# LCD_ControlRev2.net
KiCad netlist of a schematic drawn in EAGLE
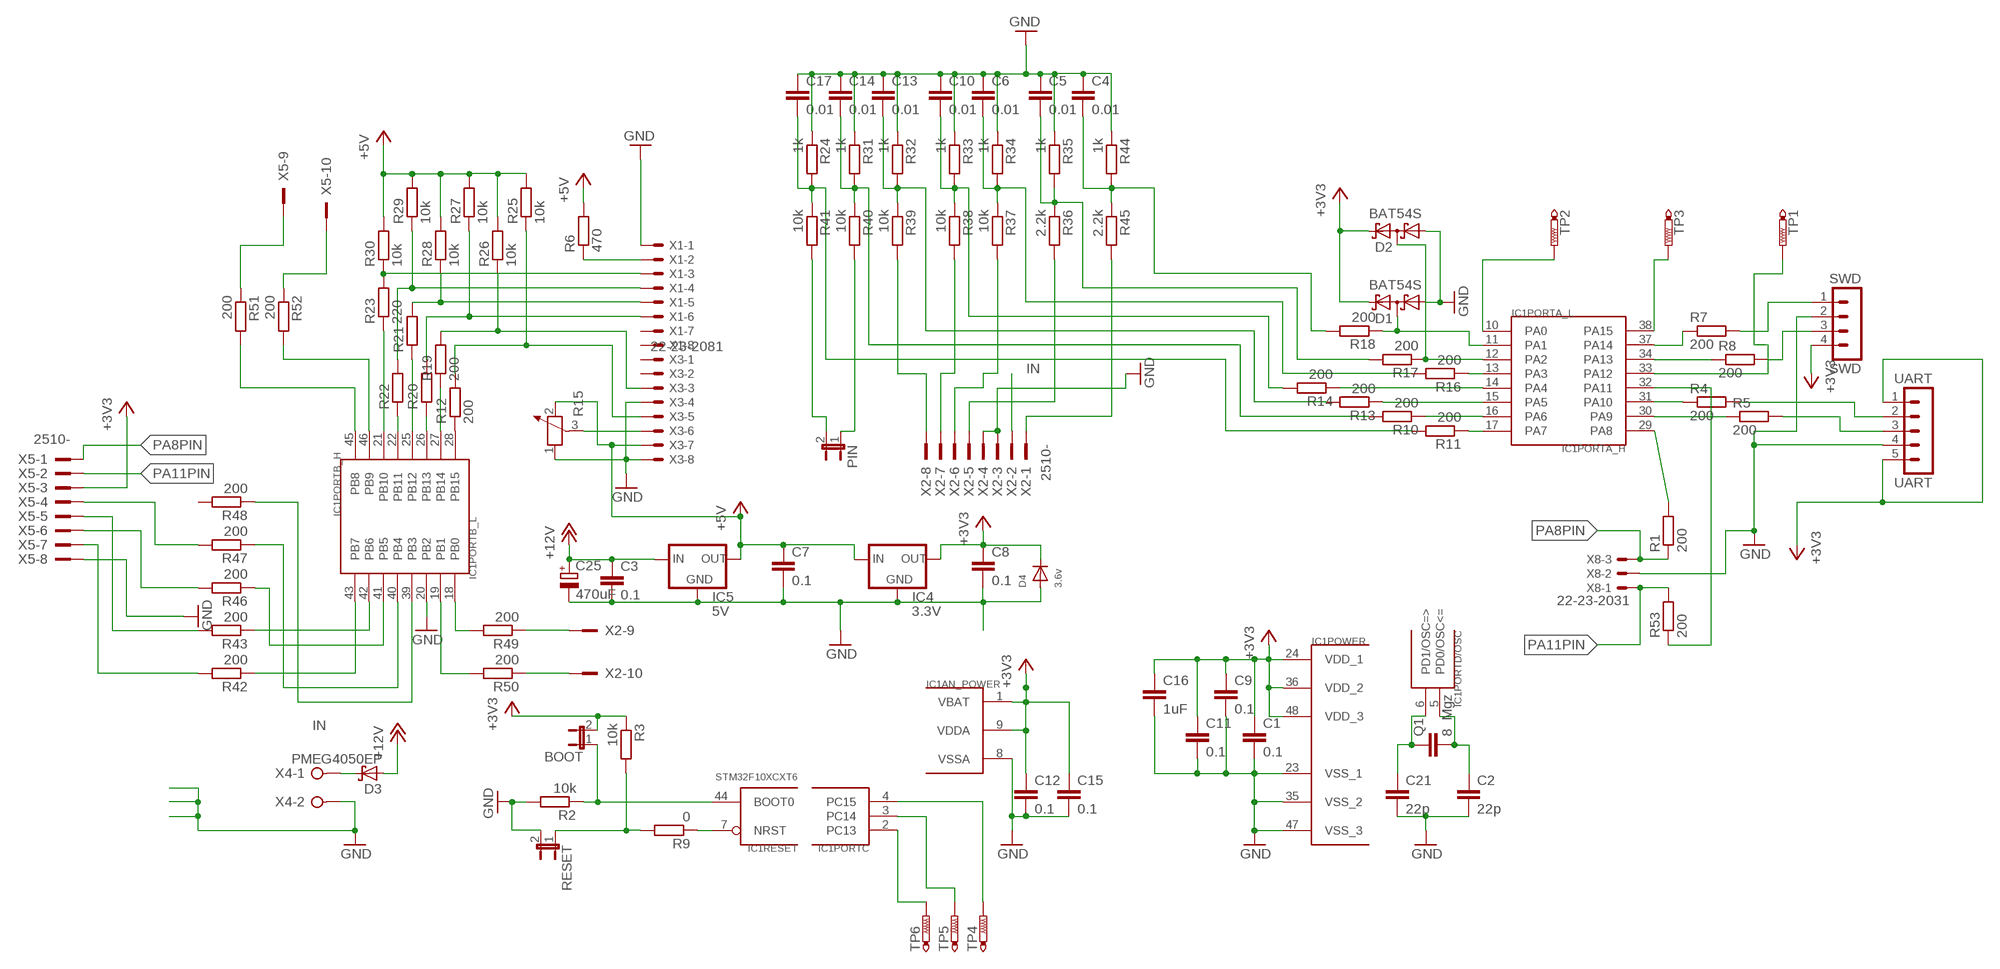
[diagram p0: schematic, sheet 1]

(export (version "E")
  (design (tool "Eeschema 10.0.6"))
  (components
    (comp (ref "BOOT")
      (value "JP1E")
      (footprint "eagle-import:JP1")
      (libsource (lib "eagle-import") (part "JP1E"))
    )
    (comp (ref "C1")
      (value "0.1")
      (footprint "eagle-import:C0402")
      (libsource (lib "eagle-import") (part "C-EUC0402"))
    )
    (comp (ref "C2")
      (value "22p")
      (footprint "eagle-import:C0603")
      (libsource (lib "eagle-import") (part "C-EUC0603"))
    )
    (comp (ref "C3")
      (value "0.1")
      (footprint "eagle-import:C1206")
      (libsource (lib "eagle-import") (part "C-EUC1206"))
    )
    (comp (ref "C4")
      (value "0.01")
      (footprint "eagle-import:C0603")
      (libsource (lib "eagle-import") (part "rcl_334_C-EUC0603"))
    )
    (comp (ref "C5")
      (value "0.01")
      (footprint "eagle-import:C0603")
      (libsource (lib "eagle-import") (part "rcl_334_C-EUC0603"))
    )
    (comp (ref "C6")
      (value "0.01")
      (footprint "eagle-import:C0603")
      (libsource (lib "eagle-import") (part "rcl_334_C-EUC0603"))
    )
    (comp (ref "C7")
      (value "0.1")
      (footprint "eagle-import:C1206")
      (libsource (lib "eagle-import") (part "C-EUC1206"))
    )
    (comp (ref "C8")
      (value "0.1")
      (footprint "eagle-import:C1206")
      (libsource (lib "eagle-import") (part "C-EUC1206"))
    )
    (comp (ref "C9")
      (value "0.1")
      (footprint "eagle-import:C0402")
      (libsource (lib "eagle-import") (part "C-EUC0402"))
    )
    (comp (ref "C10")
      (value "0.01")
      (footprint "eagle-import:C0603")
      (libsource (lib "eagle-import") (part "rcl_334_C-EUC0603"))
    )
    (comp (ref "C11")
      (value "0.1")
      (footprint "eagle-import:C0402")
      (libsource (lib "eagle-import") (part "C-EUC0402"))
    )
    (comp (ref "C12")
      (value "0.1")
      (footprint "eagle-import:C0402")
      (libsource (lib "eagle-import") (part "C-EUC0402"))
    )
    (comp (ref "C13")
      (value "0.01")
      (footprint "eagle-import:C0603")
      (libsource (lib "eagle-import") (part "rcl_334_C-EUC0603"))
    )
    (comp (ref "C14")
      (value "0.01")
      (footprint "eagle-import:C0603")
      (libsource (lib "eagle-import") (part "rcl_334_C-EUC0603"))
    )
    (comp (ref "C15")
      (value "0.1")
      (footprint "eagle-import:C0402")
      (libsource (lib "eagle-import") (part "C-EUC0402"))
    )
    (comp (ref "C16")
      (value "1uF")
      (footprint "eagle-import:C0603")
      (libsource (lib "eagle-import") (part "C-EUC0603"))
    )
    (comp (ref "C17")
      (value "0.01")
      (footprint "eagle-import:C0603")
      (libsource (lib "eagle-import") (part "rcl_334_C-EUC0603"))
    )
    (comp (ref "C21")
      (value "22p")
      (footprint "eagle-import:C0603")
      (libsource (lib "eagle-import") (part "C-EUC0603"))
    )
    (comp (ref "C25")
      (value "470uF")
      (footprint "eagle-import:E5-10,5")
      (libsource (lib "eagle-import") (part "CPOL-EUE5-10.5"))
    )
    (comp (ref "D1")
      (value "BAT54S")
      (footprint "eagle-import:SOT23")
      (libsource (lib "eagle-import") (part "BAT54S"))
    )
    (comp (ref "D2")
      (value "BAT54S")
      (footprint "eagle-import:SOT23")
      (libsource (lib "eagle-import") (part "BAT54S"))
    )
    (comp (ref "D3")
      (value "PMEG4050EP")
      (footprint "eagle-import:SOD128")
      (libsource (lib "eagle-import") (part "PMEG4050EP"))
    )
    (comp (ref "D4")
      (value "3.6v")
      (footprint "eagle-import:SOD-123")
      (libsource (lib "eagle-import") (part "DIODESOD-123"))
    )
    (comp (ref "IC1")
      (value "STM32F10XCXT6")
      (footprint "eagle-import:TQFP48")
      (libsource (lib "eagle-import") (part "STM32F10XCXT6"))
    )
    (comp (ref "IC4")
      (value "3.3V")
      (footprint "eagle-import:SOT223")
      (libsource (lib "eagle-import") (part "LM1117"))
    )
    (comp (ref "IC5")
      (value "5V")
      (footprint "eagle-import:SOT223")
      (libsource (lib "eagle-import") (part "LM1117"))
    )
    (comp (ref "PIN")
      (value "JP1E")
      (footprint "eagle-import:JP1")
      (libsource (lib "eagle-import") (part "JP1E"))
    )
    (comp (ref "Q1")
      (value "8 Mgz")
      (footprint "eagle-import:C050-024X044")
      (libsource (lib "eagle-import") (part "C-EU050-024X044"))
    )
    (comp (ref "R1")
      (value "200")
      (footprint "eagle-import:R0603")
      (libsource (lib "eagle-import") (part "R-EU_R0603"))
    )
    (comp (ref "R2")
      (value "10k")
      (footprint "eagle-import:R0603")
      (libsource (lib "eagle-import") (part "R-EU_R0603"))
    )
    (comp (ref "R3")
      (value "10k")
      (footprint "eagle-import:R0603")
      (libsource (lib "eagle-import") (part "R-EU_R0603"))
    )
    (comp (ref "R4")
      (value "200")
      (footprint "eagle-import:R0603")
      (libsource (lib "eagle-import") (part "R-EU_R0603"))
    )
    (comp (ref "R5")
      (value "200")
      (footprint "eagle-import:R0603")
      (libsource (lib "eagle-import") (part "R-EU_R0603"))
    )
    (comp (ref "R6")
      (value "470")
      (footprint "eagle-import:R0603")
      (libsource (lib "eagle-import") (part "R-EU_R0603"))
    )
    (comp (ref "R7")
      (value "200")
      (footprint "eagle-import:R0603")
      (libsource (lib "eagle-import") (part "R-EU_R0603"))
    )
    (comp (ref "R8")
      (value "200")
      (footprint "eagle-import:R0603")
      (libsource (lib "eagle-import") (part "R-EU_R0603"))
    )
    (comp (ref "R9")
      (value "0")
      (footprint "eagle-import:M1206")
      (libsource (lib "eagle-import") (part "R-EU_M1206"))
    )
    (comp (ref "R10")
      (value "200")
      (footprint "eagle-import:R0603")
      (libsource (lib "eagle-import") (part "R-EU_R0603"))
    )
    (comp (ref "R11")
      (value "200")
      (footprint "eagle-import:R0603")
      (libsource (lib "eagle-import") (part "R-EU_R0603"))
    )
    (comp (ref "R12")
      (value "200")
      (footprint "eagle-import:R0603")
      (libsource (lib "eagle-import") (part "R-EU_R0603"))
    )
    (comp (ref "R13")
      (value "200")
      (footprint "eagle-import:R0603")
      (libsource (lib "eagle-import") (part "R-EU_R0603"))
    )
    (comp (ref "R14")
      (value "200")
      (footprint "eagle-import:R0603")
      (libsource (lib "eagle-import") (part "R-EU_R0603"))
    )
    (comp (ref "R15")
      (value "POTENTIOMETER_PT-10S")
      (footprint "eagle-import:PT-10S")
      (libsource (lib "eagle-import") (part "POTENTIOMETER_PT-10S"))
    )
    (comp (ref "R16")
      (value "200")
      (footprint "eagle-import:R0603")
      (libsource (lib "eagle-import") (part "R-EU_R0603"))
    )
    (comp (ref "R17")
      (value "200")
      (footprint "eagle-import:R0603")
      (libsource (lib "eagle-import") (part "R-EU_R0603"))
    )
    (comp (ref "R18")
      (value "200")
      (footprint "eagle-import:R0603")
      (libsource (lib "eagle-import") (part "R-EU_R0603"))
    )
    (comp (ref "R19")
      (value "200")
      (footprint "eagle-import:R0603")
      (libsource (lib "eagle-import") (part "R-EU_R0603"))
    )
    (comp (ref "R20")
      (value "R-EU_R0603")
      (footprint "eagle-import:R0603")
      (libsource (lib "eagle-import") (part "R-EU_R0603"))
    )
    (comp (ref "R21")
      (value "R-EU_R0603")
      (footprint "eagle-import:R0603")
      (libsource (lib "eagle-import") (part "R-EU_R0603"))
    )
    (comp (ref "R22")
      (value "R-EU_R0603")
      (footprint "eagle-import:R0603")
      (libsource (lib "eagle-import") (part "R-EU_R0603"))
    )
    (comp (ref "R23")
      (value "220")
      (footprint "eagle-import:R0603")
      (libsource (lib "eagle-import") (part "R-EU_R0603"))
    )
    (comp (ref "R24")
      (value "1k")
      (footprint "eagle-import:R0603")
      (libsource (lib "eagle-import") (part "R-EU_R0603"))
    )
    (comp (ref "R25")
      (value "10k")
      (footprint "eagle-import:R0603")
      (libsource (lib "eagle-import") (part "R-EU_R0603"))
    )
    (comp (ref "R26")
      (value "10k")
      (footprint "eagle-import:R0603")
      (libsource (lib "eagle-import") (part "R-EU_R0603"))
    )
    (comp (ref "R27")
      (value "10k")
      (footprint "eagle-import:R0603")
      (libsource (lib "eagle-import") (part "R-EU_R0603"))
    )
    (comp (ref "R28")
      (value "10k")
      (footprint "eagle-import:R0603")
      (libsource (lib "eagle-import") (part "R-EU_R0603"))
    )
    (comp (ref "R29")
      (value "10k")
      (footprint "eagle-import:R0603")
      (libsource (lib "eagle-import") (part "R-EU_R0603"))
    )
    (comp (ref "R30")
      (value "10k")
      (footprint "eagle-import:R0603")
      (libsource (lib "eagle-import") (part "R-EU_R0603"))
    )
    (comp (ref "R31")
      (value "1k")
      (footprint "eagle-import:R0603")
      (libsource (lib "eagle-import") (part "R-EU_R0603"))
    )
    (comp (ref "R32")
      (value "1k")
      (footprint "eagle-import:R0603")
      (libsource (lib "eagle-import") (part "R-EU_R0603"))
    )
    (comp (ref "R33")
      (value "1k")
      (footprint "eagle-import:R0603")
      (libsource (lib "eagle-import") (part "R-EU_R0603"))
    )
    (comp (ref "R34")
      (value "1k")
      (footprint "eagle-import:R0603")
      (libsource (lib "eagle-import") (part "R-EU_R0603"))
    )
    (comp (ref "R35")
      (value "1k")
      (footprint "eagle-import:R0603")
      (fields (field (name "SPICEPREFIX") "R"))
      (libsource (lib "eagle-import") (part "R-EU_R0603"))
    )
    (comp (ref "R36")
      (value "2.2k")
      (footprint "eagle-import:R0603")
      (libsource (lib "eagle-import") (part "R-EU_R0603"))
    )
    (comp (ref "R37")
      (value "10k")
      (footprint "eagle-import:R0603")
      (libsource (lib "eagle-import") (part "R-EU_R0603"))
    )
    (comp (ref "R38")
      (value "10k")
      (footprint "eagle-import:R0603")
      (libsource (lib "eagle-import") (part "R-EU_R0603"))
    )
    (comp (ref "R39")
      (value "10k")
      (footprint "eagle-import:R0603")
      (libsource (lib "eagle-import") (part "R-EU_R0603"))
    )
    (comp (ref "R40")
      (value "10k")
      (footprint "eagle-import:R0603")
      (libsource (lib "eagle-import") (part "R-EU_R0603"))
    )
    (comp (ref "R41")
      (value "10k")
      (footprint "eagle-import:R0603")
      (libsource (lib "eagle-import") (part "R-EU_R0603"))
    )
    (comp (ref "R42")
      (value "200")
      (footprint "eagle-import:R0603")
      (libsource (lib "eagle-import") (part "R-EU_R0603"))
    )
    (comp (ref "R43")
      (value "200")
      (footprint "eagle-import:R0603")
      (libsource (lib "eagle-import") (part "R-EU_R0603"))
    )
    (comp (ref "R44")
      (value "1k")
      (footprint "eagle-import:R0603")
      (libsource (lib "eagle-import") (part "R-EU_R0603"))
    )
    (comp (ref "R45")
      (value "2.2k")
      (footprint "eagle-import:R0603")
      (libsource (lib "eagle-import") (part "R-EU_R0603"))
    )
    (comp (ref "R46")
      (value "200")
      (footprint "eagle-import:R0603")
      (libsource (lib "eagle-import") (part "R-EU_R0603"))
    )
    (comp (ref "R47")
      (value "200")
      (footprint "eagle-import:R0603")
      (libsource (lib "eagle-import") (part "R-EU_R0603"))
    )
    (comp (ref "R48")
      (value "200")
      (footprint "eagle-import:R0603")
      (libsource (lib "eagle-import") (part "R-EU_R0603"))
    )
    (comp (ref "R49")
      (value "200")
      (footprint "eagle-import:R0603")
      (libsource (lib "eagle-import") (part "R-EU_R0603"))
    )
    (comp (ref "R50")
      (value "200")
      (footprint "eagle-import:R0603")
      (libsource (lib "eagle-import") (part "R-EU_R0603"))
    )
    (comp (ref "R51")
      (value "200")
      (footprint "eagle-import:R0603")
      (libsource (lib "eagle-import") (part "R-EU_R0603"))
    )
    (comp (ref "R52")
      (value "200")
      (footprint "eagle-import:R0603")
      (libsource (lib "eagle-import") (part "R-EU_R0603"))
    )
    (comp (ref "R53")
      (value "200")
      (footprint "eagle-import:R0603")
      (libsource (lib "eagle-import") (part "R-EU_R0603"))
    )
    (comp (ref "RESET")
      (value "JP1E")
      (footprint "eagle-import:JP1")
      (libsource (lib "eagle-import") (part "JP1E"))
    )
    (comp (ref "SWD")
      (value "SWD")
      (footprint "eagle-import:MA04-1")
      (libsource (lib "eagle-import") (part "MA04-1"))
    )
    (comp (ref "TP1")
      (value "PTR1TP06R")
      (footprint "eagle-import:TP06R")
      (libsource (lib "eagle-import") (part "PTR1TP06R"))
    )
    (comp (ref "TP2")
      (value "PTR1TP06R")
      (footprint "eagle-import:TP06R")
      (libsource (lib "eagle-import") (part "PTR1TP06R"))
    )
    (comp (ref "TP3")
      (value "PTR1TP06R")
      (footprint "eagle-import:TP06R")
      (libsource (lib "eagle-import") (part "PTR1TP06R"))
    )
    (comp (ref "TP4")
      (value "PTR1TP06R")
      (footprint "eagle-import:TP06R")
      (libsource (lib "eagle-import") (part "PTR1TP06R"))
    )
    (comp (ref "TP5")
      (value "PTR1TP06R")
      (footprint "eagle-import:TP06R")
      (libsource (lib "eagle-import") (part "PTR1TP06R"))
    )
    (comp (ref "TP6")
      (value "PTR1TP06R")
      (footprint "eagle-import:TP06R")
      (libsource (lib "eagle-import") (part "PTR1TP06R"))
    )
    (comp (ref "UART")
      (value "UART")
      (footprint "eagle-import:MA05-1")
      (libsource (lib "eagle-import") (part "MA05-1"))
    )
    (comp (ref "X1")
      (value "22-23-2081")
      (footprint "eagle-import:22-23-2081")
      (fields (field (name "MF") "MOLEX"))
      (libsource (lib "eagle-import") (part "22-23-2081"))
    )
    (comp (ref "X2")
      (value "2510-")
      (footprint "eagle-import:PAK100_2500-10")
      (fields (field (name "MF") "3M") (field (name "MPN") "2510-6002UB"))
      (libsource (lib "eagle-import") (part "2510-"))
    )
    (comp (ref "X3")
      (value "22-23-2081")
      (footprint "eagle-import:22-23-2081")
      (fields (field (name "MF") "MOLEX"))
      (libsource (lib "eagle-import") (part "22-23-2081"))
    )
    (comp (ref "X4")
      (value "W237-02P")
      (footprint "eagle-import:W237-132")
      (libsource (lib "eagle-import") (part "W237-02P"))
    )
    (comp (ref "X5")
      (value "2510-")
      (footprint "eagle-import:PAK100_2500-10")
      (fields (field (name "MF") "3M") (field (name "MPN") "2510-6002UB"))
      (libsource (lib "eagle-import") (part "2510-"))
    )
    (comp (ref "X8")
      (value "22-23-2031")
      (footprint "eagle-import:22-23-2031")
      (fields (field (name "MF") "MOLEX"))
      (libsource (lib "eagle-import") (part "22-23-2031"))
    )
  )
  (nets
    (net (code "1") (name "+3V3") (class "Default")
      (node (ref "BOOT") (pin "2") (pinfunction "2_2") (pintype "passive"))
      (node (ref "C1") (pin "1") (pinfunction "1_1") (pintype "passive"))
      (node (ref "C11") (pin "1") (pinfunction "1_1") (pintype "passive"))
      (node (ref "C12") (pin "1") (pinfunction "1_1") (pintype "passive"))
      (node (ref "C15") (pin "1") (pinfunction "1_1") (pintype "passive"))
      (node (ref "C16") (pin "1") (pinfunction "1_1") (pintype "passive"))
      (node (ref "C8") (pin "1") (pinfunction "1_1") (pintype "passive"))
      (node (ref "C9") (pin "1") (pinfunction "1_1") (pintype "passive"))
      (node (ref "D1") (pin "2") (pinfunction "C2_2") (pintype "passive"))
      (node (ref "D2") (pin "2") (pinfunction "C2_2") (pintype "passive"))
      (node (ref "D4") (pin "C") (pinfunction "C_C") (pintype "passive"))
      (node (ref "IC1") (pin "1") (pinfunction "VBAT_1") (pintype "power_in"))
      (node (ref "IC1") (pin "24") (pinfunction "VDD_1_24") (pintype "power_in"))
      (node (ref "IC1") (pin "36") (pinfunction "VDD_2_36") (pintype "power_in"))
      (node (ref "IC1") (pin "48") (pinfunction "VDD_3_48") (pintype "power_in"))
      (node (ref "IC1") (pin "9") (pinfunction "VDDA_9") (pintype "power_in"))
      (node (ref "IC4") (pin "2") (pinfunction "OUT_2") (pintype "passive"))
      (node (ref "IC4") (pin "4") (pinfunction "OUT_4") (pintype "passive"))
      (node (ref "R3") (pin "1") (pinfunction "1_1") (pintype "passive"))
      (node (ref "SWD") (pin "4") (pinfunction "4_4") (pintype "passive"))
      (node (ref "UART") (pin "1") (pinfunction "1_1") (pintype "passive"))
      (node (ref "UART") (pin "5") (pinfunction "5_5") (pintype "passive"))
      (node (ref "X5") (pin "3") (pinfunction "KL_3") (pintype "passive"))
    )
    (net (code "2") (name "+5V") (class "Default")
      (node (ref "C7") (pin "1") (pinfunction "1_1") (pintype "passive"))
      (node (ref "IC4") (pin "3") (pinfunction "IN_3") (pintype "input"))
      (node (ref "IC5") (pin "2") (pinfunction "OUT_2") (pintype "passive"))
      (node (ref "IC5") (pin "4") (pinfunction "OUT_4") (pintype "passive"))
      (node (ref "R15") (pin "2") (pinfunction "2_2") (pintype "passive"))
      (node (ref "R25") (pin "2") (pinfunction "2_2") (pintype "passive"))
      (node (ref "R26") (pin "2") (pinfunction "2_2") (pintype "passive"))
      (node (ref "R27") (pin "2") (pinfunction "2_2") (pintype "passive"))
      (node (ref "R28") (pin "2") (pinfunction "2_2") (pintype "passive"))
      (node (ref "R29") (pin "2") (pinfunction "2_2") (pintype "passive"))
      (node (ref "R30") (pin "2") (pinfunction "2_2") (pintype "passive"))
      (node (ref "R6") (pin "2") (pinfunction "2_2") (pintype "passive"))
      (node (ref "X3") (pin "7") (pinfunction "S_7") (pintype "passive"))
    )
    (net (code "3") (name "+12V") (class "Default")
      (node (ref "C25") (pin "+") (pinfunction "+_+") (pintype "passive"))
      (node (ref "C3") (pin "1") (pinfunction "1_1") (pintype "passive"))
      (node (ref "D3") (pin "2") (pinfunction "A_2") (pintype "passive"))
      (node (ref "IC5") (pin "3") (pinfunction "IN_3") (pintype "input"))
    )
    (net (code "4") (name "/IN") (class "Default")
      (node (ref "D3") (pin "1") (pinfunction "K_1") (pintype "passive"))
      (node (ref "X2") (pin "2") (pinfunction "KL_2") (pintype "passive"))
      (node (ref "X4") (pin "1") (pinfunction "KL_1") (pintype "passive"))
    )
    (net (code "5") (name "GND") (class "Default")
      (node (ref "C1") (pin "2") (pinfunction "2_2") (pintype "passive"))
      (node (ref "C10") (pin "1") (pinfunction "1_1") (pintype "passive"))
      (node (ref "C11") (pin "2") (pinfunction "2_2") (pintype "passive"))
      (node (ref "C12") (pin "2") (pinfunction "2_2") (pintype "passive"))
      (node (ref "C13") (pin "1") (pinfunction "1_1") (pintype "passive"))
      (node (ref "C14") (pin "1") (pinfunction "1_1") (pintype "passive"))
      (node (ref "C15") (pin "2") (pinfunction "2_2") (pintype "passive"))
      (node (ref "C16") (pin "2") (pinfunction "2_2") (pintype "passive"))
      (node (ref "C17") (pin "1") (pinfunction "1_1") (pintype "passive"))
      (node (ref "C2") (pin "2") (pinfunction "2_2") (pintype "passive"))
      (node (ref "C21") (pin "2") (pinfunction "2_2") (pintype "passive"))
      (node (ref "C25") (pin "-") (pinfunction "-_-") (pintype "passive"))
      (node (ref "C3") (pin "2") (pinfunction "2_2") (pintype "passive"))
      (node (ref "C4") (pin "1") (pinfunction "1_1") (pintype "passive"))
      (node (ref "C5") (pin "1") (pinfunction "1_1") (pintype "passive"))
      (node (ref "C6") (pin "1") (pinfunction "1_1") (pintype "passive"))
      (node (ref "C7") (pin "2") (pinfunction "2_2") (pintype "passive"))
      (node (ref "C8") (pin "2") (pinfunction "2_2") (pintype "passive"))
      (node (ref "C9") (pin "2") (pinfunction "2_2") (pintype "passive"))
      (node (ref "D1") (pin "1") (pinfunction "A1_1") (pintype "passive"))
      (node (ref "D2") (pin "1") (pinfunction "A1_1") (pintype "passive"))
      (node (ref "D4") (pin "A") (pinfunction "A_A") (pintype "passive"))
      (node (ref "IC1") (pin "20") (pinfunction "PB2_20") (pintype "bidirectional"))
      (node (ref "IC1") (pin "23") (pinfunction "VSS_1_23") (pintype "power_in"))
      (node (ref "IC1") (pin "35") (pinfunction "VSS_2_35") (pintype "power_in"))
      (node (ref "IC1") (pin "47") (pinfunction "VSS_3_47") (pintype "power_in"))
      (node (ref "IC1") (pin "8") (pinfunction "VSSA_8") (pintype "power_in"))
      (node (ref "IC4") (pin "1") (pinfunction "GND_1") (pintype "input"))
      (node (ref "IC5") (pin "1") (pinfunction "GND_1") (pintype "input"))
      (node (ref "R15") (pin "1") (pinfunction "1_1") (pintype "passive"))
      (node (ref "R2") (pin "2") (pinfunction "2_2") (pintype "passive"))
      (node (ref "R24") (pin "1") (pinfunction "1_1") (pintype "passive"))
      (node (ref "R31") (pin "1") (pinfunction "1_1") (pintype "passive"))
      (node (ref "R32") (pin "1") (pinfunction "1_1") (pintype "passive"))
      (node (ref "R33") (pin "1") (pinfunction "1_1") (pintype "passive"))
      (node (ref "R34") (pin "1") (pinfunction "1_1") (pintype "passive"))
      (node (ref "R35") (pin "1") (pinfunction "1_1") (pintype "passive"))
      (node (ref "R44") (pin "1") (pinfunction "1_1") (pintype "passive"))
      (node (ref "RESET") (pin "2") (pinfunction "2_2") (pintype "passive"))
      (node (ref "SWD") (pin "2") (pinfunction "2_2") (pintype "passive"))
      (node (ref "UART") (pin "4") (pinfunction "4_4") (pintype "passive"))
      (node (ref "X1") (pin "1") (pinfunction "S_1") (pintype "passive"))
      (node (ref "X2") (pin "3") (pinfunction "KL_3") (pintype "passive"))
      (node (ref "X2") (pin "4") (pinfunction "KL_4") (pintype "passive"))
      (node (ref "X3") (pin "4") (pinfunction "S_4") (pintype "passive"))
      (node (ref "X3") (pin "8") (pinfunction "S_8") (pintype "passive"))
      (node (ref "X4") (pin "2") (pinfunction "KL_2") (pintype "passive"))
      (node (ref "X5") (pin "8") (pinfunction "KL_8") (pintype "passive"))
      (node (ref "X8") (pin "2") (pinfunction "S_2") (pintype "passive"))
    )
    (net (code "6") (name "Net-(C4-Pad2)") (class "Default")
      (node (ref "C4") (pin "2") (pinfunction "2_2") (pintype "passive"))
      (node (ref "R18") (pin "2") (pinfunction "2_2") (pintype "passive"))
      (node (ref "R44") (pin "2") (pinfunction "2_2") (pintype "passive"))
      (node (ref "R45") (pin "1") (pinfunction "1_1") (pintype "passive"))
    )
    (net (code "7") (name "Net-(C5-Pad2)") (class "Default")
      (node (ref "C5") (pin "2") (pinfunction "2_2") (pintype "passive"))
      (node (ref "R17") (pin "2") (pinfunction "2_2") (pintype "passive"))
      (node (ref "R35") (pin "2") (pinfunction "2_2") (pintype "passive"))
      (node (ref "R36") (pin "1") (pinfunction "1_1") (pintype "passive"))
    )
    (net (code "8") (name "Net-(C6-Pad2)") (class "Default")
      (node (ref "C6") (pin "2") (pinfunction "2_2") (pintype "passive"))
      (node (ref "R16") (pin "2") (pinfunction "2_2") (pintype "passive"))
      (node (ref "R34") (pin "2") (pinfunction "2_2") (pintype "passive"))
      (node (ref "R37") (pin "1") (pinfunction "1_1") (pintype "passive"))
    )
    (net (code "9") (name "Net-(C10-Pad2)") (class "Default")
      (node (ref "C10") (pin "2") (pinfunction "2_2") (pintype "passive"))
      (node (ref "R14") (pin "2") (pinfunction "2_2") (pintype "passive"))
      (node (ref "R33") (pin "2") (pinfunction "2_2") (pintype "passive"))
      (node (ref "R38") (pin "1") (pinfunction "1_1") (pintype "passive"))
    )
    (net (code "10") (name "Net-(C13-Pad2)") (class "Default")
      (node (ref "C13") (pin "2") (pinfunction "2_2") (pintype "passive"))
      (node (ref "R13") (pin "2") (pinfunction "2_2") (pintype "passive"))
      (node (ref "R32") (pin "2") (pinfunction "2_2") (pintype "passive"))
      (node (ref "R39") (pin "1") (pinfunction "1_1") (pintype "passive"))
    )
    (net (code "11") (name "Net-(C14-Pad2)") (class "Default")
      (node (ref "C14") (pin "2") (pinfunction "2_2") (pintype "passive"))
      (node (ref "R10") (pin "2") (pinfunction "2_2") (pintype "passive"))
      (node (ref "R31") (pin "2") (pinfunction "2_2") (pintype "passive"))
      (node (ref "R40") (pin "1") (pinfunction "1_1") (pintype "passive"))
    )
    (net (code "12") (name "Net-(C17-Pad2)") (class "Default")
      (node (ref "C17") (pin "2") (pinfunction "2_2") (pintype "passive"))
      (node (ref "R11") (pin "2") (pinfunction "2_2") (pintype "passive"))
      (node (ref "R24") (pin "2") (pinfunction "2_2") (pintype "passive"))
      (node (ref "R41") (pin "1") (pinfunction "1_1") (pintype "passive"))
    )
    (net (code "13") (name "Net-(D1-C1A2)") (class "Default")
      (node (ref "D1") (pin "3") (pinfunction "C1A2_3") (pintype "passive"))
      (node (ref "IC1") (pin "11") (pinfunction "PA1_11") (pintype "bidirectional"))
      (node (ref "R18") (pin "1") (pinfunction "1_1") (pintype "passive"))
    )
    (net (code "14") (name "Net-(D2-C1A2)") (class "Default")
      (node (ref "D2") (pin "3") (pinfunction "C1A2_3") (pintype "passive"))
      (node (ref "IC1") (pin "12") (pinfunction "PA2_12") (pintype "bidirectional"))
      (node (ref "R17") (pin "1") (pinfunction "1_1") (pintype "passive"))
    )
    (net (code "15") (name "Net-(IC1B-PA8)") (class "Default")
      (node (ref "IC1") (pin "29") (pinfunction "PA8_29") (pintype "bidirectional"))
      (node (ref "R1") (pin "2") (pinfunction "2_2") (pintype "passive"))
    )
    (net (code "16") (name "Net-(IC1B-PA9)") (class "Default")
      (node (ref "IC1") (pin "30") (pinfunction "PA9_30") (pintype "bidirectional"))
      (node (ref "R5") (pin "1") (pinfunction "1_1") (pintype "passive"))
    )
    (net (code "17") (name "Net-(IC1B-PA10)") (class "Default")
      (node (ref "IC1") (pin "31") (pinfunction "PA10_31") (pintype "bidirectional"))
      (node (ref "R4") (pin "1") (pinfunction "1_1") (pintype "passive"))
    )
    (net (code "18") (name "Net-(IC1B-PA11)") (class "Default")
      (node (ref "IC1") (pin "32") (pinfunction "PA11_32") (pintype "bidirectional"))
      (node (ref "R53") (pin "1") (pinfunction "1_1") (pintype "passive"))
    )
    (net (code "19") (name "Net-(IC1B-PA12)") (class "Default")
      (node (ref "IC1") (pin "33") (pinfunction "PA12_33") (pintype "bidirectional"))
      (node (ref "TP1") (pin "TP") (pinfunction "TP_TP") (pintype "input"))
    )
    (net (code "20") (name "Net-(IC1B-PA13)") (class "Default")
      (node (ref "IC1") (pin "34") (pinfunction "PA13_34") (pintype "bidirectional"))
      (node (ref "R8") (pin "1") (pinfunction "1_1") (pintype "passive"))
    )
    (net (code "21") (name "Net-(IC1B-PA14)") (class "Default")
      (node (ref "IC1") (pin "37") (pinfunction "PA14_37") (pintype "bidirectional"))
      (node (ref "R7") (pin "1") (pinfunction "1_1") (pintype "passive"))
    )
    (net (code "22") (name "Net-(IC1B-PA15)") (class "Default")
      (node (ref "IC1") (pin "38") (pinfunction "PA15_38") (pintype "bidirectional"))
      (node (ref "TP3") (pin "TP") (pinfunction "TP_TP") (pintype "input"))
    )
    (net (code "23") (name "Net-(IC1C-PA0)") (class "Default")
      (node (ref "IC1") (pin "10") (pinfunction "PA0_10") (pintype "bidirectional"))
      (node (ref "TP2") (pin "TP") (pinfunction "TP_TP") (pintype "input"))
    )
    (net (code "24") (name "Net-(IC1C-PA3)") (class "Default")
      (node (ref "IC1") (pin "13") (pinfunction "PA3_13") (pintype "bidirectional"))
      (node (ref "R16") (pin "1") (pinfunction "1_1") (pintype "passive"))
    )
    (net (code "25") (name "Net-(IC1C-PA4)") (class "Default")
      (node (ref "IC1") (pin "14") (pinfunction "PA4_14") (pintype "bidirectional"))
      (node (ref "R14") (pin "1") (pinfunction "1_1") (pintype "passive"))
    )
    (net (code "26") (name "Net-(IC1C-PA5)") (class "Default")
      (node (ref "IC1") (pin "15") (pinfunction "PA5_15") (pintype "bidirectional"))
      (node (ref "R13") (pin "1") (pinfunction "1_1") (pintype "passive"))
    )
    (net (code "27") (name "Net-(IC1C-PA6)") (class "Default")
      (node (ref "IC1") (pin "16") (pinfunction "PA6_16") (pintype "bidirectional"))
      (node (ref "R10") (pin "1") (pinfunction "1_1") (pintype "passive"))
    )
    (net (code "28") (name "Net-(IC1C-PA7)") (class "Default")
      (node (ref "IC1") (pin "17") (pinfunction "PA7_17") (pintype "bidirectional"))
      (node (ref "R11") (pin "1") (pinfunction "1_1") (pintype "passive"))
    )
    (net (code "29") (name "Net-(IC1D-PB8)") (class "Default")
      (node (ref "IC1") (pin "45") (pinfunction "PB8_45") (pintype "bidirectional"))
      (node (ref "R51") (pin "2") (pinfunction "2_2") (pintype "passive"))
    )
    (net (code "30") (name "Net-(IC1D-PB9)") (class "Default")
      (node (ref "IC1") (pin "46") (pinfunction "PB9_46") (pintype "bidirectional"))
      (node (ref "R52") (pin "2") (pinfunction "2_2") (pintype "passive"))
    )
    (net (code "31") (name "Net-(IC1D-PB10)") (class "Default")
      (node (ref "IC1") (pin "21") (pinfunction "PB10_21") (pintype "bidirectional"))
      (node (ref "R23") (pin "1") (pinfunction "1_1") (pintype "passive"))
    )
    (net (code "32") (name "Net-(IC1D-PB11)") (class "Default")
      (node (ref "IC1") (pin "22") (pinfunction "PB11_22") (pintype "bidirectional"))
      (node (ref "R22") (pin "1") (pinfunction "1_1") (pintype "passive"))
    )
    (net (code "33") (name "Net-(IC1D-PB12)") (class "Default")
      (node (ref "IC1") (pin "25") (pinfunction "PB12_25") (pintype "bidirectional"))
      (node (ref "R21") (pin "1") (pinfunction "1_1") (pintype "passive"))
    )
    (net (code "34") (name "Net-(IC1D-PB13)") (class "Default")
      (node (ref "IC1") (pin "26") (pinfunction "PB13_26") (pintype "bidirectional"))
      (node (ref "R20") (pin "1") (pinfunction "1_1") (pintype "passive"))
    )
    (net (code "35") (name "Net-(IC1D-PB14)") (class "Default")
      (node (ref "IC1") (pin "27") (pinfunction "PB14_27") (pintype "bidirectional"))
      (node (ref "R19") (pin "1") (pinfunction "1_1") (pintype "passive"))
    )
    (net (code "36") (name "Net-(IC1D-PB15)") (class "Default")
      (node (ref "IC1") (pin "28") (pinfunction "PB15_28") (pintype "bidirectional"))
      (node (ref "R12") (pin "1") (pinfunction "1_1") (pintype "passive"))
    )
    (net (code "37") (name "Net-(IC1E-PB0)") (class "Default")
      (node (ref "IC1") (pin "18") (pinfunction "PB0_18") (pintype "bidirectional"))
      (node (ref "R49") (pin "2") (pinfunction "2_2") (pintype "passive"))
    )
    (net (code "38") (name "Net-(IC1E-PB1)") (class "Default")
      (node (ref "IC1") (pin "19") (pinfunction "PB1_19") (pintype "bidirectional"))
      (node (ref "R50") (pin "2") (pinfunction "2_2") (pintype "passive"))
    )
    (net (code "39") (name "Net-(IC1E-PB3)") (class "Default")
      (node (ref "IC1") (pin "39") (pinfunction "PB3_39") (pintype "bidirectional"))
      (node (ref "R48") (pin "1") (pinfunction "1_1") (pintype "passive"))
    )
    (net (code "40") (name "Net-(IC1E-PB4)") (class "Default")
      (node (ref "IC1") (pin "40") (pinfunction "PB4_40") (pintype "bidirectional"))
      (node (ref "R47") (pin "1") (pinfunction "1_1") (pintype "passive"))
    )
    (net (code "41") (name "Net-(IC1E-PB5)") (class "Default")
      (node (ref "IC1") (pin "41") (pinfunction "PB5_41") (pintype "bidirectional"))
      (node (ref "R46") (pin "1") (pinfunction "1_1") (pintype "passive"))
    )
    (net (code "42") (name "Net-(IC1E-PB6)") (class "Default")
      (node (ref "IC1") (pin "42") (pinfunction "PB6_42") (pintype "bidirectional"))
      (node (ref "R43") (pin "1") (pinfunction "1_1") (pintype "passive"))
    )
    (net (code "43") (name "Net-(IC1E-PB7)") (class "Default")
      (node (ref "IC1") (pin "43") (pinfunction "PB7_43") (pintype "bidirectional"))
      (node (ref "R42") (pin "1") (pinfunction "1_1") (pintype "passive"))
    )
    (net (code "44") (name "Net-(IC1F-PC13)") (class "Default")
      (node (ref "IC1") (pin "2") (pinfunction "PC13_2") (pintype "bidirectional"))
      (node (ref "TP6") (pin "TP") (pinfunction "TP_TP") (pintype "input"))
    )
    (net (code "45") (name "Net-(IC1F-PC14)") (class "Default")
      (node (ref "IC1") (pin "3") (pinfunction "PC14_3") (pintype "bidirectional"))
      (node (ref "TP5") (pin "TP") (pinfunction "TP_TP") (pintype "input"))
    )
    (net (code "46") (name "Net-(IC1F-PC15)") (class "Default")
      (node (ref "IC1") (pin "4") (pinfunction "PC15_4") (pintype "bidirectional"))
      (node (ref "TP4") (pin "TP") (pinfunction "TP_TP") (pintype "input"))
    )
    (net (code "47") (name "Net-(IC1G-PD0{slash}OSC<=)") (class "Default")
      (node (ref "C2") (pin "1") (pinfunction "1_1") (pintype "passive"))
      (node (ref "IC1") (pin "5") (pinfunction "PD0/OSC<=_5") (pintype "bidirectional"))
      (node (ref "Q1") (pin "2") (pinfunction "2_2") (pintype "passive"))
    )
    (net (code "48") (name "Net-(IC1G-PD1{slash}OSC=>)") (class "Default")
      (node (ref "C21") (pin "1") (pinfunction "1_1") (pintype "passive"))
      (node (ref "IC1") (pin "6") (pinfunction "PD1/OSC=>_6") (pintype "bidirectional"))
      (node (ref "Q1") (pin "1") (pinfunction "1_1") (pintype "passive"))
    )
    (net (code "49") (name "Net-(IC1I-BOOT0)") (class "Default")
      (node (ref "BOOT") (pin "1") (pinfunction "1_1") (pintype "passive"))
      (node (ref "IC1") (pin "44") (pinfunction "BOOT0_44") (pintype "input"))
      (node (ref "R2") (pin "1") (pinfunction "1_1") (pintype "passive"))
    )
    (net (code "50") (name "Net-(IC1I-NRST)") (class "Default")
      (node (ref "IC1") (pin "7") (pinfunction "NRST_7") (pintype "input"))
      (node (ref "R9") (pin "1") (pinfunction "1_1") (pintype "passive"))
    )
    (net (code "51") (name "Net-(PIN-Pad1)") (class "Default")
      (node (ref "PIN") (pin "1") (pinfunction "1_1") (pintype "passive"))
      (node (ref "R40") (pin "2") (pinfunction "2_2") (pintype "passive"))
    )
    (net (code "52") (name "Net-(PIN-Pad2)") (class "Default")
      (node (ref "PIN") (pin "2") (pinfunction "2_2") (pintype "passive"))
      (node (ref "R41") (pin "2") (pinfunction "2_2") (pintype "passive"))
    )
    (net (code "53") (name "Net-(R3-Pad2)") (class "Default")
      (node (ref "R3") (pin "2") (pinfunction "2_2") (pintype "passive"))
      (node (ref "R9") (pin "2") (pinfunction "2_2") (pintype "passive"))
      (node (ref "RESET") (pin "1") (pinfunction "1_1") (pintype "passive"))
    )
    (net (code "54") (name "Net-(R4-Pad2)") (class "Default")
      (node (ref "R4") (pin "2") (pinfunction "2_2") (pintype "passive"))
      (node (ref "UART") (pin "2") (pinfunction "2_2") (pintype "passive"))
    )
    (net (code "55") (name "Net-(R5-Pad2)") (class "Default")
      (node (ref "R5") (pin "2") (pinfunction "2_2") (pintype "passive"))
      (node (ref "UART") (pin "3") (pinfunction "3_3") (pintype "passive"))
    )
    (net (code "56") (name "Net-(R7-Pad2)") (class "Default")
      (node (ref "R7") (pin "2") (pinfunction "2_2") (pintype "passive"))
      (node (ref "SWD") (pin "1") (pinfunction "1_1") (pintype "passive"))
    )
    (net (code "57") (name "Net-(R8-Pad2)") (class "Default")
      (node (ref "R8") (pin "2") (pinfunction "2_2") (pintype "passive"))
      (node (ref "SWD") (pin "3") (pinfunction "3_3") (pintype "passive"))
    )
    (net (code "58") (name "Net-(X1B-S)") (class "Default")
      (node (ref "R6") (pin "1") (pinfunction "1_1") (pintype "passive"))
      (node (ref "X1") (pin "2") (pinfunction "S_2") (pintype "passive"))
    )
    (net (code "59") (name "Net-(X1C-S)") (class "Default")
      (node (ref "R23") (pin "2") (pinfunction "2_2") (pintype "passive"))
      (node (ref "R30") (pin "1") (pinfunction "1_1") (pintype "passive"))
      (node (ref "X1") (pin "3") (pinfunction "S_3") (pintype "passive"))
    )
    (net (code "60") (name "Net-(X1D-S)") (class "Default")
      (node (ref "R22") (pin "2") (pinfunction "2_2") (pintype "passive"))
      (node (ref "R29") (pin "1") (pinfunction "1_1") (pintype "passive"))
      (node (ref "X1") (pin "4") (pinfunction "S_4") (pintype "passive"))
    )
    (net (code "61") (name "Net-(X1E-S)") (class "Default")
      (node (ref "R21") (pin "2") (pinfunction "2_2") (pintype "passive"))
      (node (ref "R28") (pin "1") (pinfunction "1_1") (pintype "passive"))
      (node (ref "X1") (pin "5") (pinfunction "S_5") (pintype "passive"))
    )
    (net (code "62") (name "Net-(X1F-S)") (class "Default")
      (node (ref "R20") (pin "2") (pinfunction "2_2") (pintype "passive"))
      (node (ref "R27") (pin "1") (pinfunction "1_1") (pintype "passive"))
      (node (ref "X1") (pin "6") (pinfunction "S_6") (pintype "passive"))
    )
    (net (code "63") (name "Net-(X2A-KL)") (class "Default")
      (node (ref "R45") (pin "2") (pinfunction "2_2") (pintype "passive"))
      (node (ref "X2") (pin "1") (pinfunction "KL_1") (pintype "passive"))
    )
    (net (code "64") (name "Net-(X2B-KL)") (class "Default")
      (node (ref "R50") (pin "1") (pinfunction "1_1") (pintype "passive"))
      (node (ref "X2") (pin "10") (pinfunction "KL_10") (pintype "passive"))
    )
    (net (code "65") (name "Net-(X2F-KL)") (class "Default")
      (node (ref "R36") (pin "2") (pinfunction "2_2") (pintype "passive"))
      (node (ref "X2") (pin "5") (pinfunction "KL_5") (pintype "passive"))
    )
    (net (code "66") (name "Net-(X2G-KL)") (class "Default")
      (node (ref "R37") (pin "2") (pinfunction "2_2") (pintype "passive"))
      (node (ref "X2") (pin "6") (pinfunction "KL_6") (pintype "passive"))
    )
    (net (code "67") (name "Net-(X2H-KL)") (class "Default")
      (node (ref "R38") (pin "2") (pinfunction "2_2") (pintype "passive"))
      (node (ref "X2") (pin "7") (pinfunction "KL_7") (pintype "passive"))
    )
    (net (code "68") (name "Net-(X2I-KL)") (class "Default")
      (node (ref "R39") (pin "2") (pinfunction "2_2") (pintype "passive"))
      (node (ref "X2") (pin "8") (pinfunction "KL_8") (pintype "passive"))
    )
    (net (code "69") (name "Net-(X2J-KL)") (class "Default")
      (node (ref "R49") (pin "1") (pinfunction "1_1") (pintype "passive"))
      (node (ref "X2") (pin "9") (pinfunction "KL_9") (pintype "passive"))
    )
    (net (code "70") (name "Net-(X3C-S)") (class "Default")
      (node (ref "R19") (pin "2") (pinfunction "2_2") (pintype "passive"))
      (node (ref "R26") (pin "1") (pinfunction "1_1") (pintype "passive"))
      (node (ref "X3") (pin "3") (pinfunction "S_3") (pintype "passive"))
    )
    (net (code "71") (name "Net-(X3E-S)") (class "Default")
      (node (ref "R12") (pin "2") (pinfunction "2_2") (pintype "passive"))
      (node (ref "R25") (pin "1") (pinfunction "1_1") (pintype "passive"))
      (node (ref "X3") (pin "5") (pinfunction "S_5") (pintype "passive"))
    )
    (net (code "72") (name "Net-(X3F-S)") (class "Default")
      (node (ref "R15") (pin "3") (pinfunction "3_3") (pintype "passive"))
      (node (ref "X3") (pin "6") (pinfunction "S_6") (pintype "passive"))
    )
    (net (code "73") (name "Net-(X5B-KL)") (class "Default")
      (node (ref "R52") (pin "1") (pinfunction "1_1") (pintype "passive"))
      (node (ref "X5") (pin "10") (pinfunction "KL_10") (pintype "passive"))
    )
    (net (code "74") (name "Net-(X5E-KL)") (class "Default")
      (node (ref "R47") (pin "2") (pinfunction "2_2") (pintype "passive"))
      (node (ref "X5") (pin "4") (pinfunction "KL_4") (pintype "passive"))
    )
    (net (code "75") (name "Net-(X5F-KL)") (class "Default")
      (node (ref "R43") (pin "2") (pinfunction "2_2") (pintype "passive"))
      (node (ref "X5") (pin "5") (pinfunction "KL_5") (pintype "passive"))
    )
    (net (code "76") (name "Net-(X5G-KL)") (class "Default")
      (node (ref "R46") (pin "2") (pinfunction "2_2") (pintype "passive"))
      (node (ref "X5") (pin "6") (pinfunction "KL_6") (pintype "passive"))
    )
    (net (code "77") (name "Net-(X5H-KL)") (class "Default")
      (node (ref "R42") (pin "2") (pinfunction "2_2") (pintype "passive"))
      (node (ref "X5") (pin "7") (pinfunction "KL_7") (pintype "passive"))
    )
    (net (code "78") (name "Net-(X5J-KL)") (class "Default")
      (node (ref "R51") (pin "1") (pinfunction "1_1") (pintype "passive"))
      (node (ref "X5") (pin "9") (pinfunction "KL_9") (pintype "passive"))
    )
    (net (code "79") (name "PA8PIN") (class "Default")
      (node (ref "R1") (pin "1") (pinfunction "1_1") (pintype "passive"))
      (node (ref "X5") (pin "1") (pinfunction "KL_1") (pintype "passive"))
      (node (ref "X8") (pin "3") (pinfunction "S_3") (pintype "passive"))
    )
    (net (code "80") (name "PA11PIN") (class "Default")
      (node (ref "R53") (pin "2") (pinfunction "2_2") (pintype "passive"))
      (node (ref "X5") (pin "2") (pinfunction "KL_2") (pintype "passive"))
      (node (ref "X8") (pin "1") (pinfunction "S_1") (pintype "passive"))
    )
    (net (code "81") (name "unconnected-(R48-Pad2)") (class "Default")
      (node (ref "R48") (pin "2") (pinfunction "2_2") (pintype "passive"))
    )
    (net (code "82") (name "unconnected-(X1G-S-Pad7)") (class "Default")
      (node (ref "X1") (pin "7") (pinfunction "S_7") (pintype "passive"))
    )
    (net (code "83") (name "unconnected-(X1H-S-Pad8)") (class "Default")
      (node (ref "X1") (pin "8") (pinfunction "S_8") (pintype "passive"))
    )
    (net (code "84") (name "unconnected-(X3A-S-Pad1)") (class "Default")
      (node (ref "X3") (pin "1") (pinfunction "S_1") (pintype "passive"))
    )
    (net (code "85") (name "unconnected-(X3B-S-Pad2)") (class "Default")
      (node (ref "X3") (pin "2") (pinfunction "S_2") (pintype "passive"))
    )
  )
)
